# Qwiic_Boost.net
KiCad netlist of a schematic drawn in EAGLE
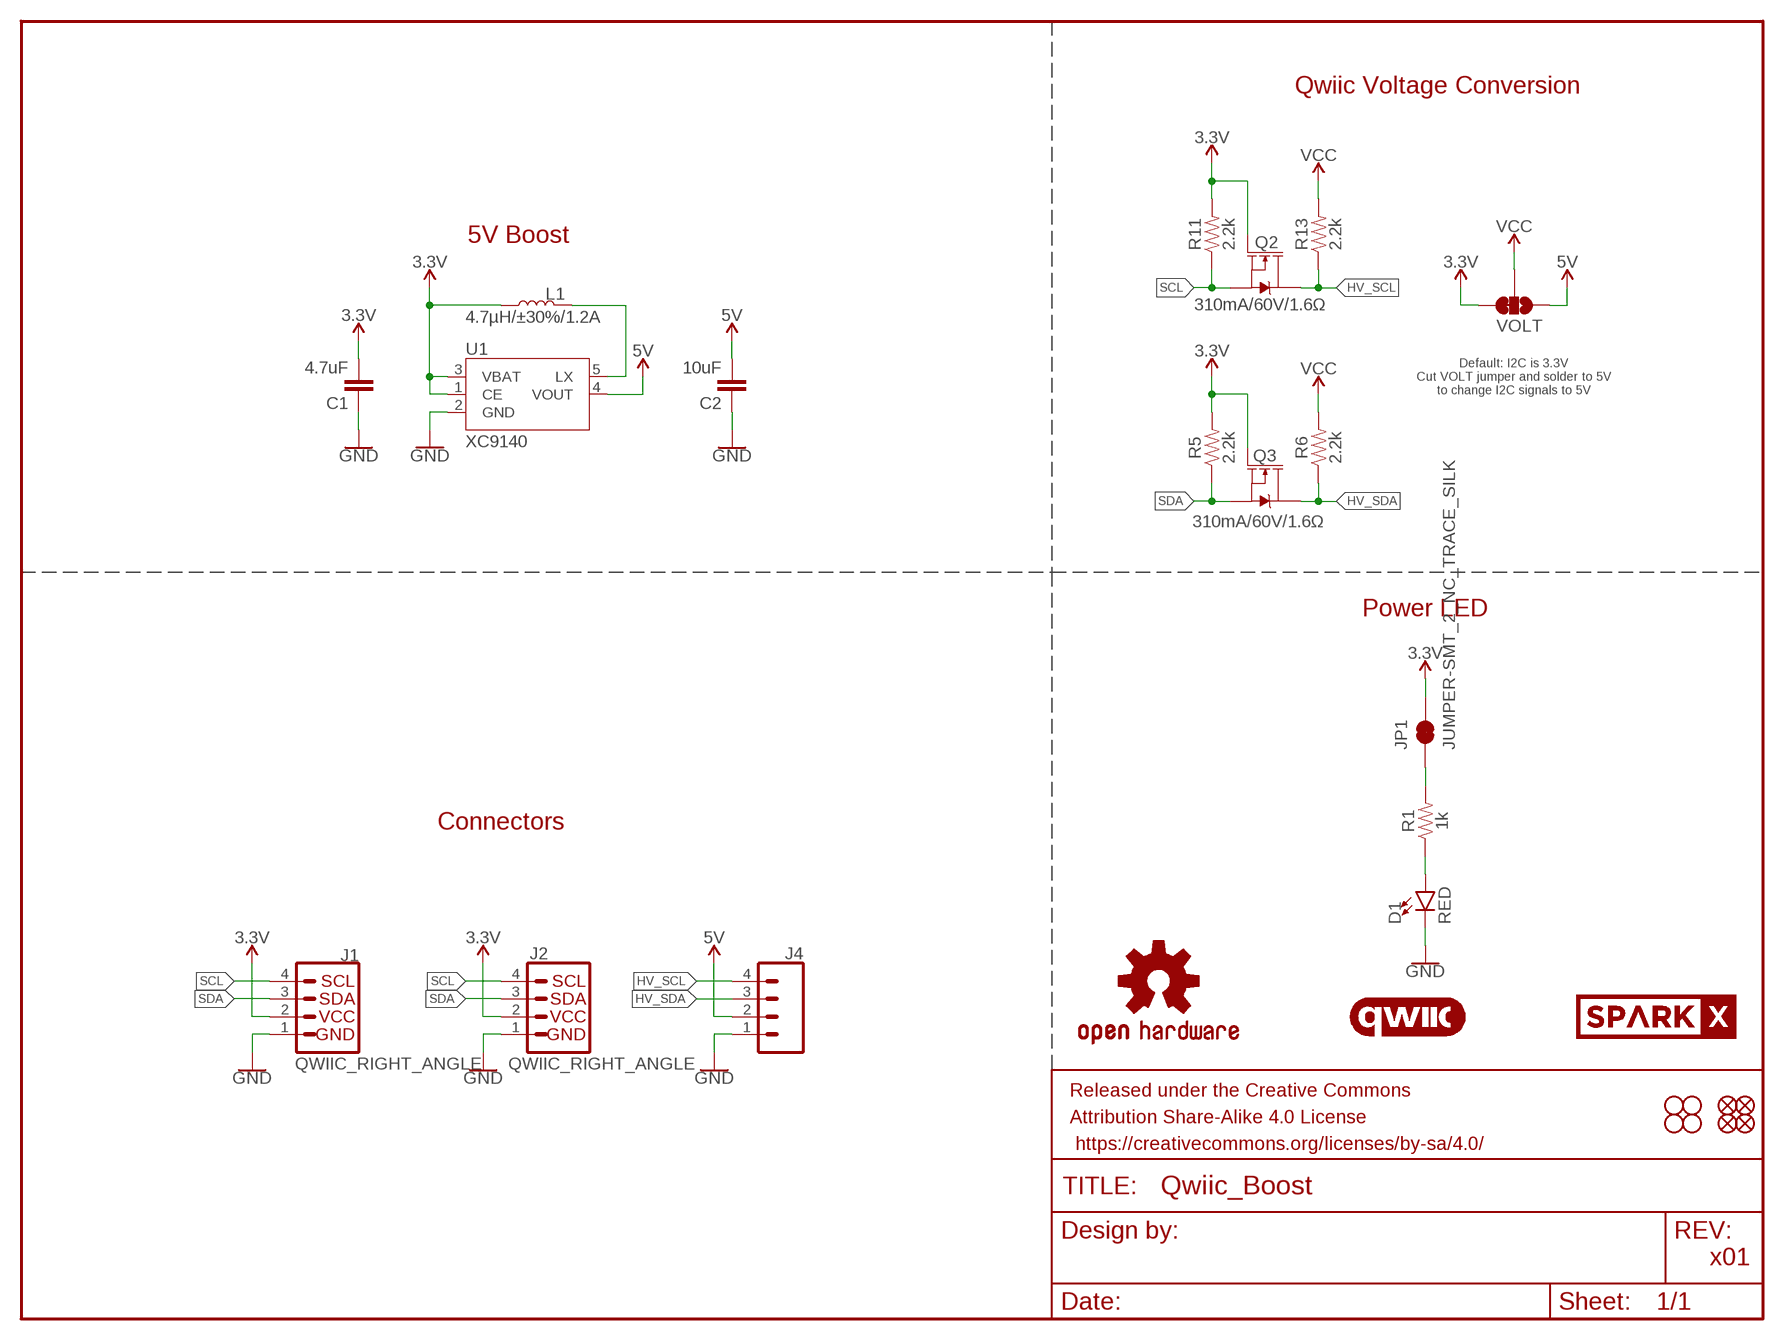
[diagram p0: schematic, sheet 1]

(export (version "E")
  (design (tool "Eeschema 10.0.6"))
  (components
    (comp (ref "C1")
      (value "4.7uF")
      (footprint "eagle-import:0603")
      (libsource (lib "eagle-import") (part "4.7UF-0603-6.3V-(10%)"))
    )
    (comp (ref "C2")
      (value "10uF")
      (footprint "eagle-import:0603")
      (libsource (lib "eagle-import") (part "10UF-0603-6.3V-20%"))
    )
    (comp (ref "D1")
      (value "RED")
      (footprint "eagle-import:LED-0603")
      (libsource (lib "eagle-import") (part "LED-RED0603"))
    )
    (comp (ref "FD1")
      (value "FIDUCIAL1X2")
      (footprint "eagle-import:FIDUCIAL-1X2")
      (libsource (lib "eagle-import") (part "FIDUCIAL1X2"))
    )
    (comp (ref "FD2")
      (value "FIDUCIAL1X2")
      (footprint "eagle-import:FIDUCIAL-1X2")
      (libsource (lib "eagle-import") (part "FIDUCIAL1X2"))
    )
    (comp (ref "FD3")
      (value "FIDUCIAL1X2")
      (footprint "eagle-import:FIDUCIAL-1X2")
      (libsource (lib "eagle-import") (part "FIDUCIAL1X2"))
    )
    (comp (ref "FD4")
      (value "FIDUCIAL1X2")
      (footprint "eagle-import:FIDUCIAL-1X2")
      (libsource (lib "eagle-import") (part "FIDUCIAL1X2"))
    )
    (comp (ref "FRAME1")
      (value "FRAME-LETTER")
      (footprint "eagle-import:CREATIVE_COMMONS")
      (libsource (lib "eagle-import") (part "FRAME-LETTER"))
    )
    (comp (ref "H1")
      (value "STAND-OFF")
      (footprint "eagle-import:STAND-OFF")
      (libsource (lib "eagle-import") (part "STAND-OFF"))
    )
    (comp (ref "H2")
      (value "STAND-OFF")
      (footprint "eagle-import:STAND-OFF")
      (libsource (lib "eagle-import") (part "STAND-OFF"))
    )
    (comp (ref "H3")
      (value "STAND-OFF")
      (footprint "eagle-import:STAND-OFF")
      (libsource (lib "eagle-import") (part "STAND-OFF"))
    )
    (comp (ref "H4")
      (value "STAND-OFF")
      (footprint "eagle-import:STAND-OFF")
      (libsource (lib "eagle-import") (part "STAND-OFF"))
    )
    (comp (ref "J1")
      (value "QWIIC_RIGHT_ANGLE")
      (footprint "eagle-import:JST04_1MM_RA")
      (libsource (lib "eagle-import") (part "QWIIC_CONNECTORJS-1MM"))
    )
    (comp (ref "J2")
      (value "QWIIC_RIGHT_ANGLE")
      (footprint "eagle-import:JST04_1MM_RA")
      (libsource (lib "eagle-import") (part "QWIIC_CONNECTORJS-1MM"))
    )
    (comp (ref "J4")
      (value "CONN_041X04_NO_SILK_NO_POP")
      (footprint "eagle-import:1X04_NO_SILK")
      (libsource (lib "eagle-import") (part "CONN_041X04_NO_SILK_NO_POP"))
    )
    (comp (ref "JP1")
      (value "JUMPER-SMT_2_NC_TRACE_SILK")
      (footprint "eagle-import:SMT-JUMPER_2_NC_TRACE_SILK")
      (libsource (lib "eagle-import") (part "JUMPER-SMT_2_NC_TRACE_SILK"))
    )
    (comp (ref "L1")
      (value "4.7µH/±30%/1.2A")
      (footprint "eagle-import:INDUCTOR_4.7UH")
      (libsource (lib "eagle-import") (part "INDUCTOR-CDRH-4.7UH"))
    )
    (comp (ref "LOGO1")
      (value "QWIIC_LOGO_CONNECTOR")
      (footprint "eagle-import:QWIIC_5.5MM")
      (libsource (lib "eagle-import") (part "QWIIC_LOGO_CONNECTOR"))
    )
    (comp (ref "LOGO2")
      (value "OSHW-LOGOMINI")
      (footprint "eagle-import:OSHW-LOGO-MINI")
      (libsource (lib "eagle-import") (part "OSHW-LOGOMINI"))
    )
    (comp (ref "Q2")
      (value "310mA/60V/1.6Ω")
      (footprint "eagle-import:SOT323")
      (libsource (lib "eagle-import") (part "MOSFET-NCH-2N7002PW"))
    )
    (comp (ref "Q3")
      (value "310mA/60V/1.6Ω")
      (footprint "eagle-import:SOT323")
      (libsource (lib "eagle-import") (part "MOSFET-NCH-2N7002PW"))
    )
    (comp (ref "R1")
      (value "1k")
      (footprint "eagle-import:0603@1")
      (libsource (lib "eagle-import") (part "1KOHM-0603-1/10W-1%"))
    )
    (comp (ref "R5")
      (value "2.2k")
      (footprint "eagle-import:0603")
      (libsource (lib "eagle-import") (part "2.2KOHM-0603-1/10W-1%"))
    )
    (comp (ref "R6")
      (value "2.2k")
      (footprint "eagle-import:0603")
      (libsource (lib "eagle-import") (part "2.2KOHM-0603-1/10W-1%"))
    )
    (comp (ref "R11")
      (value "2.2k")
      (footprint "eagle-import:0603")
      (libsource (lib "eagle-import") (part "2.2KOHM-0603-1/10W-1%"))
    )
    (comp (ref "R13")
      (value "2.2k")
      (footprint "eagle-import:0603")
      (libsource (lib "eagle-import") (part "2.2KOHM-0603-1/10W-1%"))
    )
    (comp (ref "U$8")
      (value "SPARKX-LOGO4")
      (footprint "eagle-import:SPARKX-MEDIUM")
      (libsource (lib "eagle-import") (part "SPARKX-LOGO4"))
    )
    (comp (ref "U1")
      (value "XC9140")
      (footprint "eagle-import:SOT23-5")
      (libsource (lib "eagle-import") (part "XC9140"))
    )
    (comp (ref "VOLT")
      (value "JUMPER-SMT_3_1-NC_TRACE_SILK")
      (footprint "eagle-import:SMT-JUMPER_3_1-NC_TRACE_SILK")
      (libsource (lib "eagle-import") (part "JUMPER-SMT_3_1-NC_TRACE_SILK"))
    )
  )
  (nets
    (net (code "1") (name "3.3V") (class "Default")
      (node (ref "C1") (pin "2") (pinfunction "2_2") (pintype "passive"))
      (node (ref "J1") (pin "2") (pinfunction "2_2") (pintype "power_in"))
      (node (ref "J2") (pin "2") (pinfunction "2_2") (pintype "power_in"))
      (node (ref "JP1") (pin "2") (pinfunction "2_2") (pintype "passive"))
      (node (ref "L1") (pin "P$2") (pinfunction "2_P$2") (pintype "passive"))
      (node (ref "Q2") (pin "1") (pinfunction "G_1") (pintype "bidirectional"))
      (node (ref "Q3") (pin "1") (pinfunction "G_1") (pintype "bidirectional"))
      (node (ref "R11") (pin "2") (pinfunction "2_2") (pintype "passive"))
      (node (ref "R5") (pin "2") (pinfunction "2_2") (pintype "passive"))
      (node (ref "U1") (pin "1") (pinfunction "CE_1") (pintype "input"))
      (node (ref "U1") (pin "3") (pinfunction "VBAT_3") (pintype "power_in"))
      (node (ref "VOLT") (pin "3") (pinfunction "3_3") (pintype "passive"))
    )
    (net (code "2") (name "5V") (class "Default")
      (node (ref "C2") (pin "2") (pinfunction "2_2") (pintype "passive"))
      (node (ref "J4") (pin "2") (pinfunction "2_2") (pintype "passive"))
      (node (ref "U1") (pin "4") (pinfunction "VOUT_4") (pintype "output"))
      (node (ref "VOLT") (pin "1") (pinfunction "1_1") (pintype "passive"))
    )
    (net (code "3") (name "GND") (class "Default")
      (node (ref "C1") (pin "1") (pinfunction "1_1") (pintype "passive"))
      (node (ref "C2") (pin "1") (pinfunction "1_1") (pintype "passive"))
      (node (ref "D1") (pin "C") (pinfunction "C_C") (pintype "passive"))
      (node (ref "J1") (pin "1") (pinfunction "1_1") (pintype "power_in"))
      (node (ref "J2") (pin "1") (pinfunction "1_1") (pintype "power_in"))
      (node (ref "J4") (pin "1") (pinfunction "1_1") (pintype "passive"))
      (node (ref "U1") (pin "2") (pinfunction "GND_2") (pintype "power_in"))
    )
    (net (code "4") (name "HV_SCL") (class "Default")
      (node (ref "J4") (pin "4") (pinfunction "4_4") (pintype "passive"))
      (node (ref "Q2") (pin "3") (pinfunction "D_3") (pintype "bidirectional"))
      (node (ref "R13") (pin "1") (pinfunction "1_1") (pintype "passive"))
    )
    (net (code "5") (name "HV_SDA") (class "Default")
      (node (ref "J4") (pin "3") (pinfunction "3_3") (pintype "passive"))
      (node (ref "Q3") (pin "3") (pinfunction "D_3") (pintype "bidirectional"))
      (node (ref "R6") (pin "1") (pinfunction "1_1") (pintype "passive"))
    )
    (net (code "6") (name "Net-(D1-PadA)") (class "Default")
      (node (ref "D1") (pin "A") (pinfunction "A_A") (pintype "passive"))
      (node (ref "R1") (pin "1") (pinfunction "1_1") (pintype "passive"))
    )
    (net (code "7") (name "Net-(JP1-Pad1)") (class "Default")
      (node (ref "JP1") (pin "1") (pinfunction "1_1") (pintype "passive"))
      (node (ref "R1") (pin "2") (pinfunction "2_2") (pintype "passive"))
    )
    (net (code "8") (name "Net-(L1-1)") (class "Default")
      (node (ref "L1") (pin "P$1") (pinfunction "1_P$1") (pintype "passive"))
      (node (ref "U1") (pin "5") (pinfunction "LX_5") (pintype "input"))
    )
    (net (code "9") (name "SCL") (class "Default")
      (node (ref "J1") (pin "4") (pinfunction "4_4") (pintype "passive"))
      (node (ref "J2") (pin "4") (pinfunction "4_4") (pintype "passive"))
      (node (ref "Q2") (pin "2") (pinfunction "S_2") (pintype "bidirectional"))
      (node (ref "R11") (pin "1") (pinfunction "1_1") (pintype "passive"))
    )
    (net (code "10") (name "SDA") (class "Default")
      (node (ref "J1") (pin "3") (pinfunction "3_3") (pintype "passive"))
      (node (ref "J2") (pin "3") (pinfunction "3_3") (pintype "passive"))
      (node (ref "Q3") (pin "2") (pinfunction "S_2") (pintype "bidirectional"))
      (node (ref "R5") (pin "1") (pinfunction "1_1") (pintype "passive"))
    )
    (net (code "11") (name "VCC") (class "Default")
      (node (ref "R13") (pin "2") (pinfunction "2_2") (pintype "passive"))
      (node (ref "R6") (pin "2") (pinfunction "2_2") (pintype "passive"))
      (node (ref "VOLT") (pin "2") (pinfunction "2_2") (pintype "passive"))
    )
  )
)
